# Toll_Controller_Unit_1st_Iteration.net
KiCad netlist of a schematic drawn in EAGLE
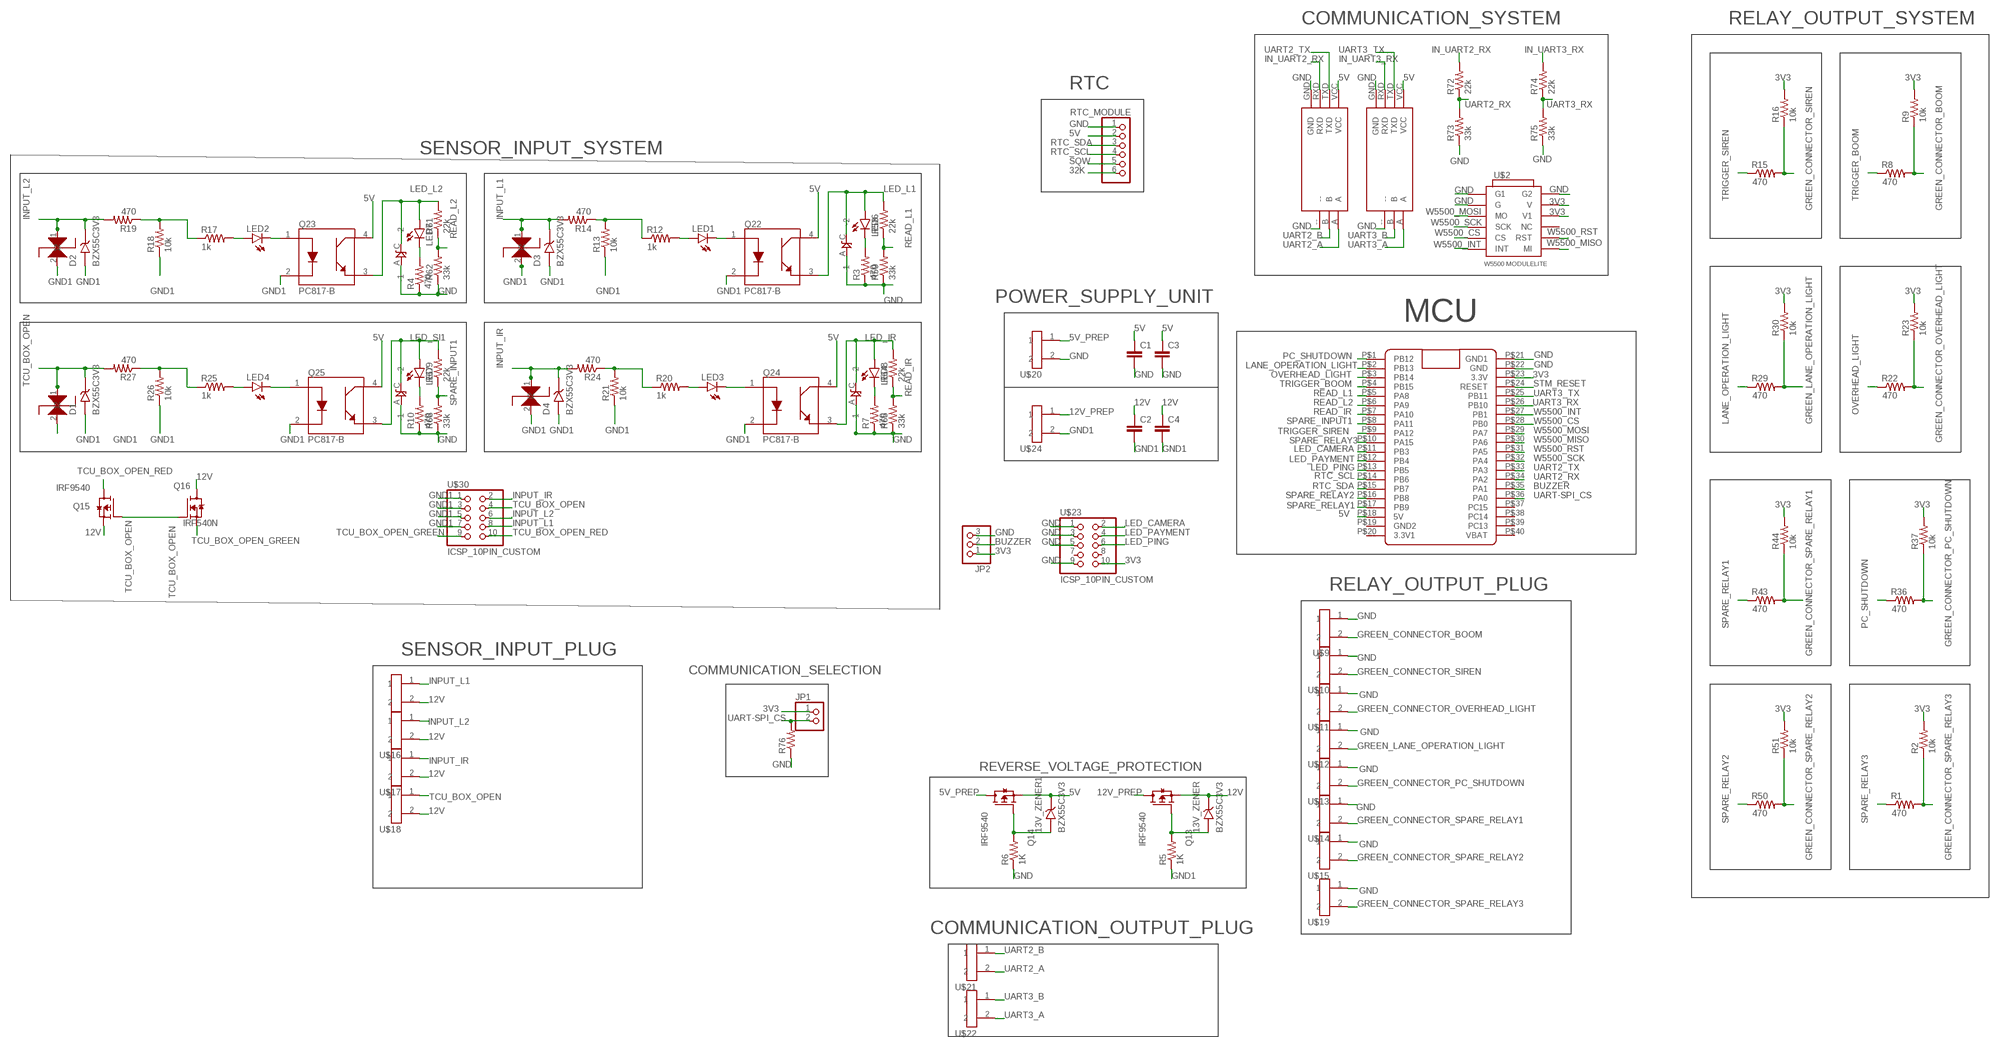
[diagram p0: schematic, sheet 1]

(export (version "E")
  (design (tool "Eeschema 10.0.6"))
  (components
    (comp (ref "13V_ZENER")
      (value "BZX55C3V3")
      (footprint "eagle-import:DIOAD928W47L399D179")
      (fields (field (name "MF") "Vishay Semiconductor") (field (name "MP") "BZX55C3V3-TR"))
      (libsource (lib "eagle-import") (part "BZX55C3V3"))
    )
    (comp (ref "13V_ZENER1")
      (value "BZX55C3V3")
      (footprint "eagle-import:DIOAD928W47L399D179")
      (fields (field (name "MF") "Vishay Semiconductor") (field (name "MP") "BZX55C3V3-TR"))
      (libsource (lib "eagle-import") (part "BZX55C3V3"))
    )
    (comp (ref "C1")
      (value "CAPACITOR")
      (footprint "eagle-import:CAPACITOR")
      (libsource (lib "eagle-import") (part "CAPACITOR"))
    )
    (comp (ref "C2")
      (value "CAPACITOR")
      (footprint "eagle-import:CAPACITOR")
      (libsource (lib "eagle-import") (part "CAPACITOR"))
    )
    (comp (ref "C3")
      (value "CAPACITOR")
      (footprint "eagle-import:CAPACITOR")
      (libsource (lib "eagle-import") (part "CAPACITOR"))
    )
    (comp (ref "C4")
      (value "CAPACITOR")
      (footprint "eagle-import:CAPACITOR")
      (libsource (lib "eagle-import") (part "CAPACITOR"))
    )
    (comp (ref "D1")
      (value "BZX55C3V3")
      (footprint "eagle-import:DIOAD928W47L399D179")
      (fields (field (name "MF") "Vishay Semiconductor") (field (name "MP") "BZX55C3V3-TR"))
      (libsource (lib "eagle-import") (part "BZX55C3V3"))
    )
    (comp (ref "D2")
      (value "BZX55C3V3")
      (footprint "eagle-import:DIOAD928W47L399D179")
      (fields (field (name "MF") "Vishay Semiconductor") (field (name "MP") "BZX55C3V3-TR"))
      (libsource (lib "eagle-import") (part "BZX55C3V3"))
    )
    (comp (ref "D3")
      (value "BZX55C3V3")
      (footprint "eagle-import:DIOAD928W47L399D179")
      (fields (field (name "MF") "Vishay Semiconductor") (field (name "MP") "BZX55C3V3-TR"))
      (libsource (lib "eagle-import") (part "BZX55C3V3"))
    )
    (comp (ref "D4")
      (value "BZX55C3V3")
      (footprint "eagle-import:DIOAD928W47L399D179")
      (fields (field (name "MF") "Vishay Semiconductor") (field (name "MP") "BZX55C3V3-TR"))
      (libsource (lib "eagle-import") (part "BZX55C3V3"))
    )
    (comp (ref "JP1")
      (value "PINHD-1X2")
      (footprint "eagle-import:1X02")
      (libsource (lib "eagle-import") (part "PINHD-1X2"))
    )
    (comp (ref "JP2")
      (value "PINHD-1X3")
      (footprint "eagle-import:1X03")
      (libsource (lib "eagle-import") (part "PINHD-1X3"))
    )
    (comp (ref "LED1")
      (value "LED")
      (footprint "eagle-import:LED")
      (libsource (lib "eagle-import") (part "LED"))
    )
    (comp (ref "LED2")
      (value "LED")
      (footprint "eagle-import:LED")
      (libsource (lib "eagle-import") (part "LED"))
    )
    (comp (ref "LED3")
      (value "LED")
      (footprint "eagle-import:LED")
      (libsource (lib "eagle-import") (part "LED"))
    )
    (comp (ref "LED4")
      (value "LED")
      (footprint "eagle-import:LED")
      (libsource (lib "eagle-import") (part "LED"))
    )
    (comp (ref "LED6")
      (value "LED")
      (footprint "eagle-import:LED")
      (libsource (lib "eagle-import") (part "LED"))
    )
    (comp (ref "LED7")
      (value "LED")
      (footprint "eagle-import:LED")
      (libsource (lib "eagle-import") (part "LED"))
    )
    (comp (ref "LED8")
      (value "LED")
      (footprint "eagle-import:LED")
      (libsource (lib "eagle-import") (part "LED"))
    )
    (comp (ref "LED9")
      (value "LED")
      (footprint "eagle-import:LED")
      (libsource (lib "eagle-import") (part "LED"))
    )
    (comp (ref "Q13")
      (value "IRF9540")
      (footprint "eagle-import:TO254P1052X465X1989-3")
      (fields (field (name "MF") "Vishay Siliconix"))
      (libsource (lib "eagle-import") (part "IRF9540"))
    )
    (comp (ref "Q14")
      (value "IRF9540")
      (footprint "eagle-import:TO254P1052X465X1989-3")
      (fields (field (name "MF") "Vishay Siliconix"))
      (libsource (lib "eagle-import") (part "IRF9540"))
    )
    (comp (ref "Q15")
      (value "IRF9540")
      (footprint "eagle-import:TO254P1052X465X1989-3")
      (fields (field (name "MF") "Vishay Siliconix"))
      (libsource (lib "eagle-import") (part "IRF9540"))
    )
    (comp (ref "Q16")
      (value "IRF540N")
      (footprint "eagle-import:TO254P1054X469X1930-3")
      (fields (field (name "MF") "Infineon Technologies"))
      (libsource (lib "eagle-import") (part "IRF540N"))
    )
    (comp (ref "Q22")
      (value "PC817-B")
      (footprint "eagle-import:DIP762W50P254L650H455Q4B")
      (fields (field (name "MF") "American Bright"))
      (libsource (lib "eagle-import") (part "PC817-B"))
    )
    (comp (ref "Q23")
      (value "PC817-B")
      (footprint "eagle-import:DIP762W50P254L650H455Q4B")
      (fields (field (name "MF") "American Bright"))
      (libsource (lib "eagle-import") (part "PC817-B"))
    )
    (comp (ref "Q24")
      (value "PC817-B")
      (footprint "eagle-import:DIP762W50P254L650H455Q4B")
      (fields (field (name "MF") "American Bright"))
      (libsource (lib "eagle-import") (part "PC817-B"))
    )
    (comp (ref "Q25")
      (value "PC817-B")
      (footprint "eagle-import:DIP762W50P254L650H455Q4B")
      (fields (field (name "MF") "American Bright"))
      (libsource (lib "eagle-import") (part "PC817-B"))
    )
    (comp (ref "R1")
      (value "470")
      (footprint "eagle-import:RESISTOR")
      (libsource (lib "eagle-import") (part "RESISTOR"))
    )
    (comp (ref "R2")
      (value "10k")
      (footprint "eagle-import:RESISTOR")
      (libsource (lib "eagle-import") (part "RESISTOR"))
    )
    (comp (ref "R3")
      (value "470")
      (footprint "eagle-import:RESISTOR")
      (libsource (lib "eagle-import") (part "RESISTOR"))
    )
    (comp (ref "R4")
      (value "470")
      (footprint "eagle-import:RESISTOR")
      (libsource (lib "eagle-import") (part "RESISTOR"))
    )
    (comp (ref "R5")
      (value "1K")
      (footprint "eagle-import:RESISTOR")
      (libsource (lib "eagle-import") (part "RESISTOR"))
    )
    (comp (ref "R6")
      (value "1K")
      (footprint "eagle-import:RESISTOR")
      (libsource (lib "eagle-import") (part "RESISTOR"))
    )
    (comp (ref "R7")
      (value "470")
      (footprint "eagle-import:RESISTOR")
      (libsource (lib "eagle-import") (part "RESISTOR"))
    )
    (comp (ref "R8")
      (value "470")
      (footprint "eagle-import:RESISTOR")
      (libsource (lib "eagle-import") (part "RESISTOR"))
    )
    (comp (ref "R9")
      (value "10k")
      (footprint "eagle-import:RESISTOR")
      (libsource (lib "eagle-import") (part "RESISTOR"))
    )
    (comp (ref "R10")
      (value "470")
      (footprint "eagle-import:RESISTOR")
      (libsource (lib "eagle-import") (part "RESISTOR"))
    )
    (comp (ref "R12")
      (value "1k")
      (footprint "eagle-import:RESISTOR")
      (libsource (lib "eagle-import") (part "RESISTOR"))
    )
    (comp (ref "R13")
      (value "10k")
      (footprint "eagle-import:RESISTOR")
      (libsource (lib "eagle-import") (part "RESISTOR"))
    )
    (comp (ref "R14")
      (value "470")
      (footprint "eagle-import:RESISTOR")
      (libsource (lib "eagle-import") (part "RESISTOR"))
    )
    (comp (ref "R15")
      (value "470")
      (footprint "eagle-import:RESISTOR")
      (libsource (lib "eagle-import") (part "RESISTOR"))
    )
    (comp (ref "R16")
      (value "10k")
      (footprint "eagle-import:RESISTOR")
      (libsource (lib "eagle-import") (part "RESISTOR"))
    )
    (comp (ref "R17")
      (value "1k")
      (footprint "eagle-import:RESISTOR")
      (libsource (lib "eagle-import") (part "RESISTOR"))
    )
    (comp (ref "R18")
      (value "10k")
      (footprint "eagle-import:RESISTOR")
      (libsource (lib "eagle-import") (part "RESISTOR"))
    )
    (comp (ref "R19")
      (value "470")
      (footprint "eagle-import:RESISTOR")
      (libsource (lib "eagle-import") (part "RESISTOR"))
    )
    (comp (ref "R20")
      (value "1k")
      (footprint "eagle-import:RESISTOR")
      (libsource (lib "eagle-import") (part "RESISTOR"))
    )
    (comp (ref "R21")
      (value "10k")
      (footprint "eagle-import:RESISTOR")
      (libsource (lib "eagle-import") (part "RESISTOR"))
    )
    (comp (ref "R22")
      (value "470")
      (footprint "eagle-import:RESISTOR")
      (libsource (lib "eagle-import") (part "RESISTOR"))
    )
    (comp (ref "R23")
      (value "10k")
      (footprint "eagle-import:RESISTOR")
      (libsource (lib "eagle-import") (part "RESISTOR"))
    )
    (comp (ref "R24")
      (value "470")
      (footprint "eagle-import:RESISTOR")
      (libsource (lib "eagle-import") (part "RESISTOR"))
    )
    (comp (ref "R25")
      (value "1k")
      (footprint "eagle-import:RESISTOR")
      (libsource (lib "eagle-import") (part "RESISTOR"))
    )
    (comp (ref "R26")
      (value "10k")
      (footprint "eagle-import:RESISTOR")
      (libsource (lib "eagle-import") (part "RESISTOR"))
    )
    (comp (ref "R27")
      (value "470")
      (footprint "eagle-import:RESISTOR")
      (libsource (lib "eagle-import") (part "RESISTOR"))
    )
    (comp (ref "R29")
      (value "470")
      (footprint "eagle-import:RESISTOR")
      (libsource (lib "eagle-import") (part "RESISTOR"))
    )
    (comp (ref "R30")
      (value "10k")
      (footprint "eagle-import:RESISTOR")
      (libsource (lib "eagle-import") (part "RESISTOR"))
    )
    (comp (ref "R36")
      (value "470")
      (footprint "eagle-import:RESISTOR")
      (libsource (lib "eagle-import") (part "RESISTOR"))
    )
    (comp (ref "R37")
      (value "10k")
      (footprint "eagle-import:RESISTOR")
      (libsource (lib "eagle-import") (part "RESISTOR"))
    )
    (comp (ref "R43")
      (value "470")
      (footprint "eagle-import:RESISTOR")
      (libsource (lib "eagle-import") (part "RESISTOR"))
    )
    (comp (ref "R44")
      (value "10k")
      (footprint "eagle-import:RESISTOR")
      (libsource (lib "eagle-import") (part "RESISTOR"))
    )
    (comp (ref "R50")
      (value "470")
      (footprint "eagle-import:RESISTOR")
      (libsource (lib "eagle-import") (part "RESISTOR"))
    )
    (comp (ref "R51")
      (value "10k")
      (footprint "eagle-import:RESISTOR")
      (libsource (lib "eagle-import") (part "RESISTOR"))
    )
    (comp (ref "R58")
      (value "22k")
      (footprint "eagle-import:RESISTOR")
      (libsource (lib "eagle-import") (part "RESISTOR"))
    )
    (comp (ref "R59")
      (value "33k")
      (footprint "eagle-import:RESISTOR")
      (libsource (lib "eagle-import") (part "RESISTOR"))
    )
    (comp (ref "R61")
      (value "22k")
      (footprint "eagle-import:RESISTOR")
      (libsource (lib "eagle-import") (part "RESISTOR"))
    )
    (comp (ref "R62")
      (value "33k")
      (footprint "eagle-import:RESISTOR")
      (libsource (lib "eagle-import") (part "RESISTOR"))
    )
    (comp (ref "R64")
      (value "22k")
      (footprint "eagle-import:RESISTOR")
      (libsource (lib "eagle-import") (part "RESISTOR"))
    )
    (comp (ref "R65")
      (value "33k")
      (footprint "eagle-import:RESISTOR")
      (libsource (lib "eagle-import") (part "RESISTOR"))
    )
    (comp (ref "R67")
      (value "22k")
      (footprint "eagle-import:RESISTOR")
      (libsource (lib "eagle-import") (part "RESISTOR"))
    )
    (comp (ref "R68")
      (value "33k")
      (footprint "eagle-import:RESISTOR")
      (libsource (lib "eagle-import") (part "RESISTOR"))
    )
    (comp (ref "R72")
      (value "22k")
      (footprint "eagle-import:RESISTOR")
      (libsource (lib "eagle-import") (part "RESISTOR"))
    )
    (comp (ref "R73")
      (value "33k")
      (footprint "eagle-import:RESISTOR")
      (libsource (lib "eagle-import") (part "RESISTOR"))
    )
    (comp (ref "R74")
      (value "22k")
      (footprint "eagle-import:RESISTOR")
      (libsource (lib "eagle-import") (part "RESISTOR"))
    )
    (comp (ref "R75")
      (value "33k")
      (footprint "eagle-import:RESISTOR")
      (libsource (lib "eagle-import") (part "RESISTOR"))
    )
    (comp (ref "R76")
      (value "RESISTOR")
      (footprint "eagle-import:RESISTOR")
      (libsource (lib "eagle-import") (part "RESISTOR"))
    )
    (comp (ref "RTC_MODULE")
      (value "PINHD-1X6")
      (footprint "eagle-import:1X06")
      (libsource (lib "eagle-import") (part "PINHD-1X6"))
    )
    (comp (ref "STM_BLUEPILL")
      (value "BLUE_PILL")
      (footprint "eagle-import:BLUE_PILL")
      (libsource (lib "eagle-import") (part "BLUE_PILL"))
    )
    (comp (ref "U$1")
      (value "1N227B")
      (footprint "eagle-import:1N227B")
      (libsource (lib "eagle-import") (part "1N227B"))
    )
    (comp (ref "U$2")
      (value "W5500_MODULELITE")
      (footprint "eagle-import:W5500_MODULELITE")
      (libsource (lib "eagle-import") (part "W5500_MODULELITE"))
    )
    (comp (ref "U$3")
      (value "1N227B")
      (footprint "eagle-import:1N227B")
      (libsource (lib "eagle-import") (part "1N227B"))
    )
    (comp (ref "U$4")
      (value "1N227B")
      (footprint "eagle-import:1N227B")
      (libsource (lib "eagle-import") (part "1N227B"))
    )
    (comp (ref "U$5")
      (value "1N227B")
      (footprint "eagle-import:1N227B")
      (libsource (lib "eagle-import") (part "1N227B"))
    )
    (comp (ref "U$6")
      (value "GREEN_PLUG_90_2")
      (footprint "eagle-import:GREEN_PLUG_90_2")
      (libsource (lib "eagle-import") (part "GREEN_PLUG_90_2"))
    )
    (comp (ref "U$7")
      (value "RS485_CHINESE")
      (footprint "eagle-import:RS485_CHINESE")
      (libsource (lib "eagle-import") (part "RS485_CHINESE"))
    )
    (comp (ref "U$8")
      (value "RS485_CHINESE")
      (footprint "eagle-import:RS485_CHINESE")
      (libsource (lib "eagle-import") (part "RS485_CHINESE"))
    )
    (comp (ref "U$9")
      (value "GREEN_PLUG_90_2")
      (footprint "eagle-import:GREEN_PLUG_90_2")
      (libsource (lib "eagle-import") (part "GREEN_PLUG_90_2"))
    )
    (comp (ref "U$10")
      (value "GREEN_PLUG_90_2")
      (footprint "eagle-import:GREEN_PLUG_90_2")
      (libsource (lib "eagle-import") (part "GREEN_PLUG_90_2"))
    )
    (comp (ref "U$11")
      (value "GREEN_PLUG_90_2")
      (footprint "eagle-import:GREEN_PLUG_90_2")
      (libsource (lib "eagle-import") (part "GREEN_PLUG_90_2"))
    )
    (comp (ref "U$12")
      (value "GREEN_PLUG_90_2")
      (footprint "eagle-import:GREEN_PLUG_90_2")
      (libsource (lib "eagle-import") (part "GREEN_PLUG_90_2"))
    )
    (comp (ref "U$13")
      (value "GREEN_PLUG_90_2")
      (footprint "eagle-import:GREEN_PLUG_90_2")
      (libsource (lib "eagle-import") (part "GREEN_PLUG_90_2"))
    )
    (comp (ref "U$14")
      (value "GREEN_PLUG_90_2")
      (footprint "eagle-import:GREEN_PLUG_90_2")
      (libsource (lib "eagle-import") (part "GREEN_PLUG_90_2"))
    )
    (comp (ref "U$15")
      (value "GREEN_PLUG_90_2")
      (footprint "eagle-import:GREEN_PLUG_90_2")
      (libsource (lib "eagle-import") (part "GREEN_PLUG_90_2"))
    )
    (comp (ref "U$16")
      (value "GREEN_PLUG_90_2")
      (footprint "eagle-import:GREEN_PLUG_90_2")
      (libsource (lib "eagle-import") (part "GREEN_PLUG_90_2"))
    )
    (comp (ref "U$17")
      (value "GREEN_PLUG_90_2")
      (footprint "eagle-import:GREEN_PLUG_90_2")
      (libsource (lib "eagle-import") (part "GREEN_PLUG_90_2"))
    )
    (comp (ref "U$18")
      (value "GREEN_PLUG_90_2")
      (footprint "eagle-import:GREEN_PLUG_90_2")
      (libsource (lib "eagle-import") (part "GREEN_PLUG_90_2"))
    )
    (comp (ref "U$19")
      (value "GREEN_PLUG_90_2")
      (footprint "eagle-import:GREEN_PLUG_90_2")
      (libsource (lib "eagle-import") (part "GREEN_PLUG_90_2"))
    )
    (comp (ref "U$20")
      (value "GREEN_PLUG_90_2")
      (footprint "eagle-import:GREEN_PLUG_90_2")
      (libsource (lib "eagle-import") (part "GREEN_PLUG_90_2"))
    )
    (comp (ref "U$21")
      (value "GREEN_PLUG_90_2")
      (footprint "eagle-import:GREEN_PLUG_90_2")
      (libsource (lib "eagle-import") (part "GREEN_PLUG_90_2"))
    )
    (comp (ref "U$22")
      (value "GREEN_PLUG_90_2")
      (footprint "eagle-import:GREEN_PLUG_90_2")
      (libsource (lib "eagle-import") (part "GREEN_PLUG_90_2"))
    )
    (comp (ref "U$23")
      (value "ICSP_10PIN_CUSTOM")
      (footprint "eagle-import:ICSP_10PIN_CUSTOM")
      (libsource (lib "eagle-import") (part "ICSP_10PIN_CUSTOM"))
    )
    (comp (ref "U$24")
      (value "GREEN_PLUG_90_2")
      (footprint "eagle-import:GREEN_PLUG_90_2")
      (libsource (lib "eagle-import") (part "GREEN_PLUG_90_2"))
    )
    (comp (ref "U$25")
      (value "1KE100A_CUSTOM")
      (footprint "eagle-import:1KE100A_CUSTOM")
      (libsource (lib "eagle-import") (part "1KE100A_CUSTOM"))
    )
    (comp (ref "U$26")
      (value "1KE100A_CUSTOM")
      (footprint "eagle-import:1KE100A_CUSTOM")
      (libsource (lib "eagle-import") (part "1KE100A_CUSTOM"))
    )
    (comp (ref "U$27")
      (value "1KE100A_CUSTOM")
      (footprint "eagle-import:1KE100A_CUSTOM")
      (libsource (lib "eagle-import") (part "1KE100A_CUSTOM"))
    )
    (comp (ref "U$28")
      (value "1KE100A_CUSTOM")
      (footprint "eagle-import:1KE100A_CUSTOM")
      (libsource (lib "eagle-import") (part "1KE100A_CUSTOM"))
    )
    (comp (ref "U$30")
      (value "ICSP_10PIN_CUSTOM")
      (footprint "eagle-import:ICSP_10PIN_CUSTOM")
      (libsource (lib "eagle-import") (part "ICSP_10PIN_CUSTOM"))
    )
  )
  (nets
    (net (code "1") (name "/3V3") (class "Default")
      (node (ref "JP1") (pin "1") (pinfunction "1_1") (pintype "passive"))
      (node (ref "JP2") (pin "1") (pinfunction "1_1") (pintype "passive"))
      (node (ref "R16") (pin "2") (pinfunction "2_2") (pintype "passive"))
      (node (ref "R2") (pin "2") (pinfunction "2_2") (pintype "passive"))
      (node (ref "R23") (pin "2") (pinfunction "2_2") (pintype "passive"))
      (node (ref "R30") (pin "2") (pinfunction "2_2") (pintype "passive"))
      (node (ref "R37") (pin "2") (pinfunction "2_2") (pintype "passive"))
      (node (ref "R44") (pin "2") (pinfunction "2_2") (pintype "passive"))
      (node (ref "R51") (pin "2") (pinfunction "2_2") (pintype "passive"))
      (node (ref "R9") (pin "2") (pinfunction "2_2") (pintype "passive"))
      (node (ref "STM_BLUEPILL") (pin "P$23") (pinfunction "3.3V_P$23") (pintype "bidirectional"))
      (node (ref "U$2") (pin "V") (pinfunction "V_V") (pintype "passive"))
      (node (ref "U$2") (pin "V1") (pinfunction "V1_V1") (pintype "passive"))
      (node (ref "U$23") (pin "10") (pinfunction "10_10") (pintype "passive"))
    )
    (net (code "2") (name "/5V") (class "Default")
      (node (ref "13V_ZENER1") (pin "C") (pinfunction "K_C") (pintype "passive"))
      (node (ref "C1") (pin "1") (pinfunction "1_1") (pintype "passive"))
      (node (ref "C3") (pin "1") (pinfunction "1_1") (pintype "passive"))
      (node (ref "Q14") (pin "3") (pinfunction "S_3") (pintype "passive"))
      (node (ref "Q22") (pin "4") (pinfunction "COLLECTOR_4") (pintype "passive"))
      (node (ref "Q23") (pin "4") (pinfunction "COLLECTOR_4") (pintype "passive"))
      (node (ref "Q24") (pin "4") (pinfunction "COLLECTOR_4") (pintype "passive"))
      (node (ref "Q25") (pin "4") (pinfunction "COLLECTOR_4") (pintype "passive"))
      (node (ref "RTC_MODULE") (pin "2") (pinfunction "2_2") (pintype "passive"))
      (node (ref "STM_BLUEPILL") (pin "P$18") (pinfunction "5V_P$18") (pintype "bidirectional"))
      (node (ref "U$7") (pin "VCC") (pinfunction "VCC_VCC") (pintype "bidirectional"))
      (node (ref "U$8") (pin "VCC") (pinfunction "VCC_VCC") (pintype "bidirectional"))
    )
    (net (code "3") (name "/5V_PREP") (class "Default")
      (node (ref "Q14") (pin "2") (pinfunction "D_2") (pintype "passive"))
      (node (ref "U$20") (pin "1") (pinfunction "1_1") (pintype "passive"))
    )
    (net (code "4") (name "/12V") (class "Default")
      (node (ref "13V_ZENER") (pin "C") (pinfunction "K_C") (pintype "passive"))
      (node (ref "C2") (pin "1") (pinfunction "1_1") (pintype "passive"))
      (node (ref "C4") (pin "1") (pinfunction "1_1") (pintype "passive"))
      (node (ref "Q13") (pin "3") (pinfunction "S_3") (pintype "passive"))
      (node (ref "Q15") (pin "3") (pinfunction "S_3") (pintype "passive"))
      (node (ref "Q16") (pin "2") (pinfunction "D_2") (pintype "passive"))
      (node (ref "U$16") (pin "2") (pinfunction "2_2") (pintype "passive"))
      (node (ref "U$17") (pin "2") (pinfunction "2_2") (pintype "passive"))
      (node (ref "U$18") (pin "2") (pinfunction "2_2") (pintype "passive"))
      (node (ref "U$6") (pin "2") (pinfunction "2_2") (pintype "passive"))
    )
    (net (code "5") (name "/12V_PREP") (class "Default")
      (node (ref "Q13") (pin "2") (pinfunction "D_2") (pintype "passive"))
      (node (ref "U$24") (pin "1") (pinfunction "1_1") (pintype "passive"))
    )
    (net (code "6") (name "/32K") (class "Default")
      (node (ref "RTC_MODULE") (pin "6") (pinfunction "6_6") (pintype "passive"))
    )
    (net (code "7") (name "/BUZZER") (class "Default")
      (node (ref "JP2") (pin "2") (pinfunction "2_2") (pintype "passive"))
      (node (ref "STM_BLUEPILL") (pin "P$35") (pinfunction "PA1_P$35") (pintype "bidirectional"))
    )
    (net (code "8") (name "/GND") (class "Default")
      (node (ref "C1") (pin "2") (pinfunction "2_2") (pintype "passive"))
      (node (ref "C3") (pin "2") (pinfunction "2_2") (pintype "passive"))
      (node (ref "JP2") (pin "3") (pinfunction "3_3") (pintype "passive"))
      (node (ref "R10") (pin "1") (pinfunction "1_1") (pintype "passive"))
      (node (ref "R3") (pin "1") (pinfunction "1_1") (pintype "passive"))
      (node (ref "R4") (pin "1") (pinfunction "1_1") (pintype "passive"))
      (node (ref "R59") (pin "1") (pinfunction "1_1") (pintype "passive"))
      (node (ref "R6") (pin "1") (pinfunction "1_1") (pintype "passive"))
      (node (ref "R62") (pin "1") (pinfunction "1_1") (pintype "passive"))
      (node (ref "R65") (pin "1") (pinfunction "1_1") (pintype "passive"))
      (node (ref "R68") (pin "1") (pinfunction "1_1") (pintype "passive"))
      (node (ref "R7") (pin "1") (pinfunction "1_1") (pintype "passive"))
      (node (ref "R73") (pin "1") (pinfunction "1_1") (pintype "passive"))
      (node (ref "R75") (pin "1") (pinfunction "1_1") (pintype "passive"))
      (node (ref "R76") (pin "1") (pinfunction "1_1") (pintype "passive"))
      (node (ref "RTC_MODULE") (pin "1") (pinfunction "1_1") (pintype "passive"))
      (node (ref "STM_BLUEPILL") (pin "P$21") (pinfunction "GND1_P$21") (pintype "power_in"))
      (node (ref "STM_BLUEPILL") (pin "P$22") (pinfunction "GND_P$22") (pintype "bidirectional"))
      (node (ref "U$1") (pin "A") (pinfunction "-1_A") (pintype "passive"))
      (node (ref "U$10") (pin "1") (pinfunction "1_1") (pintype "passive"))
      (node (ref "U$11") (pin "1") (pinfunction "1_1") (pintype "passive"))
      (node (ref "U$12") (pin "1") (pinfunction "1_1") (pintype "passive"))
      (node (ref "U$13") (pin "1") (pinfunction "1_1") (pintype "passive"))
      (node (ref "U$14") (pin "1") (pinfunction "1_1") (pintype "passive"))
      (node (ref "U$15") (pin "1") (pinfunction "1_1") (pintype "passive"))
      (node (ref "U$19") (pin "1") (pinfunction "1_1") (pintype "passive"))
      (node (ref "U$2") (pin "G") (pinfunction "G_G") (pintype "passive"))
      (node (ref "U$2") (pin "G1") (pinfunction "G1_G1") (pintype "passive"))
      (node (ref "U$2") (pin "G2") (pinfunction "G2_G2") (pintype "passive"))
      (node (ref "U$20") (pin "2") (pinfunction "2_2") (pintype "passive"))
      (node (ref "U$23") (pin "1") (pinfunction "1_1") (pintype "passive"))
      (node (ref "U$23") (pin "3") (pinfunction "3_3") (pintype "passive"))
      (node (ref "U$23") (pin "5") (pinfunction "5_5") (pintype "passive"))
      (node (ref "U$23") (pin "9") (pinfunction "9_9") (pintype "passive"))
      (node (ref "U$3") (pin "A") (pinfunction "-1_A") (pintype "passive"))
      (node (ref "U$4") (pin "A") (pinfunction "-1_A") (pintype "passive"))
      (node (ref "U$5") (pin "A") (pinfunction "-1_A") (pintype "passive"))
      (node (ref "U$7") (pin "--") (pinfunction "--_--") (pintype "bidirectional"))
      (node (ref "U$7") (pin "GND") (pinfunction "GND_GND") (pintype "bidirectional"))
      (node (ref "U$8") (pin "--") (pinfunction "--_--") (pintype "bidirectional"))
      (node (ref "U$8") (pin "GND") (pinfunction "GND_GND") (pintype "bidirectional"))
      (node (ref "U$9") (pin "1") (pinfunction "1_1") (pintype "passive"))
    )
    (net (code "9") (name "/GND1") (class "Default")
      (node (ref "C2") (pin "2") (pinfunction "2_2") (pintype "passive"))
      (node (ref "C4") (pin "2") (pinfunction "2_2") (pintype "passive"))
      (node (ref "D1") (pin "A") (pinfunction "A_A") (pintype "passive"))
      (node (ref "D2") (pin "A") (pinfunction "A_A") (pintype "passive"))
      (node (ref "D3") (pin "A") (pinfunction "A_A") (pintype "passive"))
      (node (ref "D4") (pin "A") (pinfunction "A_A") (pintype "passive"))
      (node (ref "Q22") (pin "2") (pinfunction "CATHODE_2") (pintype "passive"))
      (node (ref "Q23") (pin "2") (pinfunction "CATHODE_2") (pintype "passive"))
      (node (ref "Q24") (pin "2") (pinfunction "CATHODE_2") (pintype "passive"))
      (node (ref "Q25") (pin "2") (pinfunction "CATHODE_2") (pintype "passive"))
      (node (ref "R13") (pin "1") (pinfunction "1_1") (pintype "passive"))
      (node (ref "R18") (pin "1") (pinfunction "1_1") (pintype "passive"))
      (node (ref "R21") (pin "1") (pinfunction "1_1") (pintype "passive"))
      (node (ref "R26") (pin "1") (pinfunction "1_1") (pintype "passive"))
      (node (ref "R5") (pin "1") (pinfunction "1_1") (pintype "passive"))
      (node (ref "U$24") (pin "2") (pinfunction "2_2") (pintype "passive"))
      (node (ref "U$25") (pin "2") (pinfunction "2_2") (pintype "bidirectional"))
      (node (ref "U$26") (pin "2") (pinfunction "2_2") (pintype "bidirectional"))
      (node (ref "U$30") (pin "1") (pinfunction "1_1") (pintype "passive"))
      (node (ref "U$30") (pin "3") (pinfunction "3_3") (pintype "passive"))
      (node (ref "U$30") (pin "5") (pinfunction "5_5") (pintype "passive"))
      (node (ref "U$30") (pin "7") (pinfunction "7_7") (pintype "passive"))
    )
    (net (code "10") (name "/GREEN_CONNECTOR_BOOM") (class "Default")
      (node (ref "R8") (pin "2") (pinfunction "2_2") (pintype "passive"))
      (node (ref "R9") (pin "1") (pinfunction "1_1") (pintype "passive"))
      (node (ref "U$9") (pin "2") (pinfunction "2_2") (pintype "passive"))
    )
    (net (code "11") (name "/GREEN_CONNECTOR_OVERHEAD_LIGHT") (class "Default")
      (node (ref "R22") (pin "2") (pinfunction "2_2") (pintype "passive"))
      (node (ref "R23") (pin "1") (pinfunction "1_1") (pintype "passive"))
      (node (ref "U$11") (pin "2") (pinfunction "2_2") (pintype "passive"))
    )
    (net (code "12") (name "/GREEN_CONNECTOR_PC_SHUTDOWN") (class "Default")
      (node (ref "R36") (pin "2") (pinfunction "2_2") (pintype "passive"))
      (node (ref "R37") (pin "1") (pinfunction "1_1") (pintype "passive"))
      (node (ref "U$13") (pin "2") (pinfunction "2_2") (pintype "passive"))
    )
    (net (code "13") (name "/GREEN_CONNECTOR_SIREN") (class "Default")
      (node (ref "R15") (pin "2") (pinfunction "2_2") (pintype "passive"))
      (node (ref "R16") (pin "1") (pinfunction "1_1") (pintype "passive"))
      (node (ref "U$10") (pin "2") (pinfunction "2_2") (pintype "passive"))
    )
    (net (code "14") (name "/GREEN_CONNECTOR_SPARE_RELAY1") (class "Default")
      (node (ref "R43") (pin "2") (pinfunction "2_2") (pintype "passive"))
      (node (ref "R44") (pin "1") (pinfunction "1_1") (pintype "passive"))
      (node (ref "U$14") (pin "2") (pinfunction "2_2") (pintype "passive"))
    )
    (net (code "15") (name "/GREEN_CONNECTOR_SPARE_RELAY2") (class "Default")
      (node (ref "R50") (pin "2") (pinfunction "2_2") (pintype "passive"))
      (node (ref "R51") (pin "1") (pinfunction "1_1") (pintype "passive"))
      (node (ref "U$15") (pin "2") (pinfunction "2_2") (pintype "passive"))
    )
    (net (code "16") (name "/GREEN_CONNECTOR_SPARE_RELAY3") (class "Default")
      (node (ref "R1") (pin "2") (pinfunction "2_2") (pintype "passive"))
      (node (ref "R2") (pin "1") (pinfunction "1_1") (pintype "passive"))
      (node (ref "U$19") (pin "2") (pinfunction "2_2") (pintype "passive"))
    )
    (net (code "17") (name "/GREEN_LANE_OPERATION_LIGHT") (class "Default")
      (node (ref "R29") (pin "2") (pinfunction "2_2") (pintype "passive"))
      (node (ref "R30") (pin "1") (pinfunction "1_1") (pintype "passive"))
      (node (ref "U$12") (pin "2") (pinfunction "2_2") (pintype "passive"))
    )
    (net (code "18") (name "/INPUT_IR") (class "Default")
      (node (ref "D4") (pin "C") (pinfunction "K_C") (pintype "passive"))
      (node (ref "R24") (pin "2") (pinfunction "2_2") (pintype "passive"))
      (node (ref "U$17") (pin "1") (pinfunction "1_1") (pintype "passive"))
      (node (ref "U$27") (pin "1") (pinfunction "1_1") (pintype "bidirectional"))
      (node (ref "U$30") (pin "2") (pinfunction "2_2") (pintype "passive"))
    )
    (net (code "19") (name "/INPUT_L1") (class "Default")
      (node (ref "D3") (pin "C") (pinfunction "K_C") (pintype "passive"))
      (node (ref "R14") (pin "2") (pinfunction "2_2") (pintype "passive"))
      (node (ref "U$25") (pin "1") (pinfunction "1_1") (pintype "bidirectional"))
      (node (ref "U$30") (pin "8") (pinfunction "8_8") (pintype "passive"))
      (node (ref "U$6") (pin "1") (pinfunction "1_1") (pintype "passive"))
    )
    (net (code "20") (name "/INPUT_L2") (class "Default")
      (node (ref "D2") (pin "C") (pinfunction "K_C") (pintype "passive"))
      (node (ref "R19") (pin "2") (pinfunction "2_2") (pintype "passive"))
      (node (ref "U$16") (pin "1") (pinfunction "1_1") (pintype "passive"))
      (node (ref "U$28") (pin "1") (pinfunction "1_1") (pintype "bidirectional"))
      (node (ref "U$30") (pin "6") (pinfunction "6_6") (pintype "passive"))
    )
    (net (code "21") (name "/IN_UART2_RX") (class "Default")
      (node (ref "R72") (pin "2") (pinfunction "2_2") (pintype "passive"))
      (node (ref "U$8") (pin "RXD") (pinfunction "RXD_RXD") (pintype "bidirectional"))
    )
    (net (code "22") (name "/IN_UART3_RX") (class "Default")
      (node (ref "R74") (pin "2") (pinfunction "2_2") (pintype "passive"))
      (node (ref "U$7") (pin "RXD") (pinfunction "RXD_RXD") (pintype "bidirectional"))
    )
    (net (code "23") (name "/LANE_OPERATION_LIGHT") (class "Default")
      (node (ref "R29") (pin "1") (pinfunction "1_1") (pintype "passive"))
      (node (ref "STM_BLUEPILL") (pin "P$2") (pinfunction "PB13_P$2") (pintype "bidirectional"))
    )
    (net (code "24") (name "/LED_CAMERA") (class "Default")
      (node (ref "STM_BLUEPILL") (pin "P$11") (pinfunction "PB3_P$11") (pintype "bidirectional"))
      (node (ref "U$23") (pin "2") (pinfunction "2_2") (pintype "passive"))
    )
    (net (code "25") (name "/LED_IR") (class "Default")
      (node (ref "LED8") (pin "A") (pinfunction "A_A") (pintype "passive"))
      (node (ref "Q24") (pin "3") (pinfunction "EMITTER_3") (pintype "passive"))
      (node (ref "R64") (pin "2") (pinfunction "2_2") (pintype "passive"))
      (node (ref "U$4") (pin "C") (pinfunction "-2_C") (pintype "bidirectional"))
    )
    (net (code "26") (name "/LED_L1") (class "Default")
      (node (ref "LED6") (pin "A") (pinfunction "A_A") (pintype "passive"))
      (node (ref "Q22") (pin "3") (pinfunction "EMITTER_3") (pintype "passive"))
      (node (ref "R58") (pin "2") (pinfunction "2_2") (pintype "passive"))
      (node (ref "U$1") (pin "C") (pinfunction "-2_C") (pintype "bidirectional"))
    )
    (net (code "27") (name "/LED_L2") (class "Default")
      (node (ref "LED7") (pin "A") (pinfunction "A_A") (pintype "passive"))
      (node (ref "Q23") (pin "3") (pinfunction "EMITTER_3") (pintype "passive"))
      (node (ref "R61") (pin "2") (pinfunction "2_2") (pintype "passive"))
      (node (ref "U$3") (pin "C") (pinfunction "-2_C") (pintype "bidirectional"))
    )
    (net (code "28") (name "/LED_PAYMENT") (class "Default")
      (node (ref "STM_BLUEPILL") (pin "P$12") (pinfunction "PB4_P$12") (pintype "bidirectional"))
      (node (ref "U$23") (pin "4") (pinfunction "4_4") (pintype "passive"))
    )
    (net (code "29") (name "/LED_PING") (class "Default")
      (node (ref "STM_BLUEPILL") (pin "P$13") (pinfunction "PB5_P$13") (pintype "bidirectional"))
      (node (ref "U$23") (pin "6") (pinfunction "6_6") (pintype "passive"))
    )
    (net (code "30") (name "/LED_SI1") (class "Default")
      (node (ref "LED9") (pin "A") (pinfunction "A_A") (pintype "passive"))
      (node (ref "Q25") (pin "3") (pinfunction "EMITTER_3") (pintype "passive"))
      (node (ref "R67") (pin "2") (pinfunction "2_2") (pintype "passive"))
      (node (ref "U$5") (pin "C") (pinfunction "-2_C") (pintype "bidirectional"))
    )
    (net (code "31") (name "/OVERHEAD_LIGHT") (class "Default")
      (node (ref "R22") (pin "1") (pinfunction "1_1") (pintype "passive"))
      (node (ref "STM_BLUEPILL") (pin "P$3") (pinfunction "PB14_P$3") (pintype "bidirectional"))
    )
    (net (code "32") (name "/PC_SHUTDOWN") (class "Default")
      (node (ref "R36") (pin "1") (pinfunction "1_1") (pintype "passive"))
      (node (ref "STM_BLUEPILL") (pin "P$1") (pinfunction "PB12_P$1") (pintype "bidirectional"))
    )
    (net (code "33") (name "/READ_IR") (class "Default")
      (node (ref "R64") (pin "1") (pinfunction "1_1") (pintype "passive"))
      (node (ref "R65") (pin "2") (pinfunction "2_2") (pintype "passive"))
      (node (ref "STM_BLUEPILL") (pin "P$7") (pinfunction "PA10_P$7") (pintype "bidirectional"))
    )
    (net (code "34") (name "/READ_L1") (class "Default")
      (node (ref "R58") (pin "1") (pinfunction "1_1") (pintype "passive"))
      (node (ref "R59") (pin "2") (pinfunction "2_2") (pintype "passive"))
      (node (ref "STM_BLUEPILL") (pin "P$5") (pinfunction "PA8_P$5") (pintype "bidirectional"))
    )
    (net (code "35") (name "/READ_L2") (class "Default")
      (node (ref "R61") (pin "1") (pinfunction "1_1") (pintype "passive"))
      (node (ref "R62") (pin "2") (pinfunction "2_2") (pintype "passive"))
      (node (ref "STM_BLUEPILL") (pin "P$6") (pinfunction "PA9_P$6") (pintype "bidirectional"))
    )
    (net (code "36") (name "/RTC_SCL") (class "Default")
      (node (ref "RTC_MODULE") (pin "4") (pinfunction "4_4") (pintype "passive"))
      (node (ref "STM_BLUEPILL") (pin "P$14") (pinfunction "PB6_P$14") (pintype "bidirectional"))
    )
    (net (code "37") (name "/RTC_SDA") (class "Default")
      (node (ref "RTC_MODULE") (pin "3") (pinfunction "3_3") (pintype "passive"))
      (node (ref "STM_BLUEPILL") (pin "P$15") (pinfunction "PB7_P$15") (pintype "bidirectional"))
    )
    (net (code "38") (name "/SPARE_INPUT1") (class "Default")
      (node (ref "R67") (pin "1") (pinfunction "1_1") (pintype "passive"))
      (node (ref "R68") (pin "2") (pinfunction "2_2") (pintype "passive"))
      (node (ref "STM_BLUEPILL") (pin "P$8") (pinfunction "PA11_P$8") (pintype "bidirectional"))
    )
    (net (code "39") (name "/SPARE_RELAY1") (class "Default")
      (node (ref "R43") (pin "1") (pinfunction "1_1") (pintype "passive"))
      (node (ref "STM_BLUEPILL") (pin "P$17") (pinfunction "PB9_P$17") (pintype "bidirectional"))
    )
    (net (code "40") (name "/SPARE_RELAY2") (class "Default")
      (node (ref "R50") (pin "1") (pinfunction "1_1") (pintype "passive"))
      (node (ref "STM_BLUEPILL") (pin "P$16") (pinfunction "PB8_P$16") (pintype "bidirectional"))
    )
    (net (code "41") (name "/SPARE_RELAY3") (class "Default")
      (node (ref "R1") (pin "1") (pinfunction "1_1") (pintype "passive"))
      (node (ref "STM_BLUEPILL") (pin "P$10") (pinfunction "PA15_P$10") (pintype "bidirectional"))
    )
    (net (code "42") (name "/SQW") (class "Default")
      (node (ref "RTC_MODULE") (pin "5") (pinfunction "5_5") (pintype "passive"))
    )
    (net (code "43") (name "/STM_RESET") (class "Default")
      (node (ref "STM_BLUEPILL") (pin "P$24") (pinfunction "RESET_P$24") (pintype "bidirectional"))
    )
    (net (code "44") (name "/TCU_BOX_OPEN") (class "Default")
      (node (ref "D1") (pin "C") (pinfunction "K_C") (pintype "passive"))
      (node (ref "Q15") (pin "1") (pinfunction "G_1") (pintype "passive"))
      (node (ref "Q16") (pin "1") (pinfunction "G_1") (pintype "passive"))
      (node (ref "R27") (pin "2") (pinfunction "2_2") (pintype "passive"))
      (node (ref "U$18") (pin "1") (pinfunction "1_1") (pintype "passive"))
      (node (ref "U$26") (pin "1") (pinfunction "1_1") (pintype "bidirectional"))
      (node (ref "U$30") (pin "4") (pinfunction "4_4") (pintype "passive"))
    )
    (net (code "45") (name "/TCU_BOX_OPEN_GREEN") (class "Default")
      (node (ref "Q16") (pin "3") (pinfunction "S_3") (pintype "passive"))
      (node (ref "U$30") (pin "9") (pinfunction "9_9") (pintype "passive"))
    )
    (net (code "46") (name "/TCU_BOX_OPEN_RED") (class "Default")
      (node (ref "Q15") (pin "2") (pinfunction "D_2") (pintype "passive"))
      (node (ref "U$30") (pin "10") (pinfunction "10_10") (pintype "passive"))
    )
    (net (code "47") (name "/TRIGGER_BOOM") (class "Default")
      (node (ref "R8") (pin "1") (pinfunction "1_1") (pintype "passive"))
      (node (ref "STM_BLUEPILL") (pin "P$4") (pinfunction "PB15_P$4") (pintype "bidirectional"))
    )
    (net (code "48") (name "/TRIGGER_SIREN") (class "Default")
      (node (ref "R15") (pin "1") (pinfunction "1_1") (pintype "passive"))
      (node (ref "STM_BLUEPILL") (pin "P$9") (pinfunction "PA12_P$9") (pintype "bidirectional"))
    )
    (net (code "49") (name "/UART-SPI_CS") (class "Default")
      (node (ref "JP1") (pin "2") (pinfunction "2_2") (pintype "passive"))
      (node (ref "R76") (pin "2") (pinfunction "2_2") (pintype "passive"))
      (node (ref "STM_BLUEPILL") (pin "P$36") (pinfunction "PA0_P$36") (pintype "bidirectional"))
    )
    (net (code "50") (name "/UART2_A") (class "Default")
      (node (ref "U$21") (pin "2") (pinfunction "2_2") (pintype "passive"))
      (node (ref "U$8") (pin "A") (pinfunction "A_A") (pintype "bidirectional"))
    )
    (net (code "51") (name "/UART2_B") (class "Default")
      (node (ref "U$21") (pin "1") (pinfunction "1_1") (pintype "passive"))
      (node (ref "U$8") (pin "B") (pinfunction "B_B") (pintype "bidirectional"))
    )
    (net (code "52") (name "/UART2_RX") (class "Default")
      (node (ref "R72") (pin "1") (pinfunction "1_1") (pintype "passive"))
      (node (ref "R73") (pin "2") (pinfunction "2_2") (pintype "passive"))
      (node (ref "STM_BLUEPILL") (pin "P$34") (pinfunction "PA2_P$34") (pintype "bidirectional"))
    )
    (net (code "53") (name "/UART2_TX") (class "Default")
      (node (ref "STM_BLUEPILL") (pin "P$33") (pinfunction "PA3_P$33") (pintype "bidirectional"))
      (node (ref "U$8") (pin "TXD") (pinfunction "TXD_TXD") (pintype "bidirectional"))
    )
    (net (code "54") (name "/UART3_A") (class "Default")
      (node (ref "U$22") (pin "2") (pinfunction "2_2") (pintype "passive"))
      (node (ref "U$7") (pin "A") (pinfunction "A_A") (pintype "bidirectional"))
    )
    (net (code "55") (name "/UART3_B") (class "Default")
      (node (ref "U$22") (pin "1") (pinfunction "1_1") (pintype "passive"))
      (node (ref "U$7") (pin "B") (pinfunction "B_B") (pintype "bidirectional"))
    )
    (net (code "56") (name "/UART3_RX") (class "Default")
      (node (ref "R74") (pin "1") (pinfunction "1_1") (pintype "passive"))
      (node (ref "R75") (pin "2") (pinfunction "2_2") (pintype "passive"))
      (node (ref "STM_BLUEPILL") (pin "P$26") (pinfunction "PB10_P$26") (pintype "bidirectional"))
    )
    (net (code "57") (name "/UART3_TX") (class "Default")
      (node (ref "STM_BLUEPILL") (pin "P$25") (pinfunction "PB11_P$25") (pintype "bidirectional"))
      (node (ref "U$7") (pin "TXD") (pinfunction "TXD_TXD") (pintype "bidirectional"))
    )
    (net (code "58") (name "/W5500_CS") (class "Default")
      (node (ref "STM_BLUEPILL") (pin "P$28") (pinfunction "PB0_P$28") (pintype "bidirectional"))
      (node (ref "U$2") (pin "CS") (pinfunction "CS_CS") (pintype "passive"))
    )
    (net (code "59") (name "/W5500_INT") (class "Default")
      (node (ref "STM_BLUEPILL") (pin "P$27") (pinfunction "PB1_P$27") (pintype "bidirectional"))
      (node (ref "U$2") (pin "INT") (pinfunction "INT_INT") (pintype "passive"))
    )
    (net (code "60") (name "/W5500_MISO") (class "Default")
      (node (ref "STM_BLUEPILL") (pin "P$30") (pinfunction "PA6_P$30") (pintype "bidirectional"))
      (node (ref "U$2") (pin "MI") (pinfunction "MI_MI") (pintype "passive"))
    )
    (net (code "61") (name "/W5500_MOSI") (class "Default")
      (node (ref "STM_BLUEPILL") (pin "P$29") (pinfunction "PA7_P$29") (pintype "bidirectional"))
      (node (ref "U$2") (pin "MO") (pinfunction "MO_MO") (pintype "passive"))
    )
    (net (code "62") (name "/W5500_RST") (class "Default")
      (node (ref "STM_BLUEPILL") (pin "P$31") (pinfunction "PA5_P$31") (pintype "bidirectional"))
      (node (ref "U$2") (pin "RST") (pinfunction "RST_RST") (pintype "passive"))
    )
    (net (code "63") (name "/W5500_SCK") (class "Default")
      (node (ref "STM_BLUEPILL") (pin "P$32") (pinfunction "PA4_P$32") (pintype "bidirectional"))
      (node (ref "U$2") (pin "SCK") (pinfunction "SCK_SCK") (pintype "passive"))
    )
    (net (code "64") (name "Net-(LED1-C)") (class "Default")
      (node (ref "LED1") (pin "K") (pinfunction "C_K") (pintype "passive"))
      (node (ref "Q22") (pin "1") (pinfunction "ANODE_1") (pintype "passive"))
    )
    (net (code "65") (name "Net-(LED1-PadA)") (class "Default")
      (node (ref "LED1") (pin "A") (pinfunction "A_A") (pintype "passive"))
      (node (ref "R12") (pin "2") (pinfunction "2_2") (pintype "passive"))
    )
    (net (code "66") (name "Net-(LED2-C)") (class "Default")
      (node (ref "LED2") (pin "K") (pinfunction "C_K") (pintype "passive"))
      (node (ref "Q23") (pin "1") (pinfunction "ANODE_1") (pintype "passive"))
    )
    (net (code "67") (name "Net-(LED2-PadA)") (class "Default")
      (node (ref "LED2") (pin "A") (pinfunction "A_A") (pintype "passive"))
      (node (ref "R17") (pin "2") (pinfunction "2_2") (pintype "passive"))
    )
    (net (code "68") (name "Net-(LED3-C)") (class "Default")
      (node (ref "LED3") (pin "K") (pinfunction "C_K") (pintype "passive"))
      (node (ref "Q24") (pin "1") (pinfunction "ANODE_1") (pintype "passive"))
    )
    (net (code "69") (name "Net-(LED3-PadA)") (class "Default")
      (node (ref "LED3") (pin "A") (pinfunction "A_A") (pintype "passive"))
      (node (ref "R20") (pin "2") (pinfunction "2_2") (pintype "passive"))
    )
    (net (code "70") (name "Net-(LED4-C)") (class "Default")
      (node (ref "LED4") (pin "K") (pinfunction "C_K") (pintype "passive"))
      (node (ref "Q25") (pin "1") (pinfunction "ANODE_1") (pintype "passive"))
    )
    (net (code "71") (name "Net-(LED4-PadA)") (class "Default")
      (node (ref "LED4") (pin "A") (pinfunction "A_A") (pintype "passive"))
      (node (ref "R25") (pin "2") (pinfunction "2_2") (pintype "passive"))
    )
    (net (code "72") (name "Net-(LED6-C)") (class "Default")
      (node (ref "LED6") (pin "K") (pinfunction "C_K") (pintype "passive"))
      (node (ref "R3") (pin "2") (pinfunction "2_2") (pintype "passive"))
    )
    (net (code "73") (name "Net-(LED7-C)") (class "Default")
      (node (ref "LED7") (pin "K") (pinfunction "C_K") (pintype "passive"))
      (node (ref "R4") (pin "2") (pinfunction "2_2") (pintype "passive"))
    )
    (net (code "74") (name "Net-(LED8-C)") (class "Default")
      (node (ref "LED8") (pin "K") (pinfunction "C_K") (pintype "passive"))
      (node (ref "R7") (pin "2") (pinfunction "2_2") (pintype "passive"))
    )
    (net (code "75") (name "Net-(LED9-C)") (class "Default")
      (node (ref "LED9") (pin "K") (pinfunction "C_K") (pintype "passive"))
      (node (ref "R10") (pin "2") (pinfunction "2_2") (pintype "passive"))
    )
    (net (code "76") (name "Net-(Q13-G)") (class "Default")
      (node (ref "13V_ZENER") (pin "A") (pinfunction "A_A") (pintype "passive"))
      (node (ref "Q13") (pin "1") (pinfunction "G_1") (pintype "passive"))
      (node (ref "R5") (pin "2") (pinfunction "2_2") (pintype "passive"))
    )
    (net (code "77") (name "Net-(Q14-G)") (class "Default")
      (node (ref "13V_ZENER1") (pin "A") (pinfunction "A_A") (pintype "passive"))
      (node (ref "Q14") (pin "1") (pinfunction "G_1") (pintype "passive"))
      (node (ref "R6") (pin "2") (pinfunction "2_2") (pintype "passive"))
    )
    (net (code "78") (name "Net-(R12-Pad1)") (class "Default")
      (node (ref "R12") (pin "1") (pinfunction "1_1") (pintype "passive"))
      (node (ref "R13") (pin "2") (pinfunction "2_2") (pintype "passive"))
      (node (ref "R14") (pin "1") (pinfunction "1_1") (pintype "passive"))
    )
    (net (code "79") (name "Net-(R17-Pad1)") (class "Default")
      (node (ref "R17") (pin "1") (pinfunction "1_1") (pintype "passive"))
      (node (ref "R18") (pin "2") (pinfunction "2_2") (pintype "passive"))
      (node (ref "R19") (pin "1") (pinfunction "1_1") (pintype "passive"))
    )
    (net (code "80") (name "Net-(R20-Pad1)") (class "Default")
      (node (ref "R20") (pin "1") (pinfunction "1_1") (pintype "passive"))
      (node (ref "R21") (pin "2") (pinfunction "2_2") (pintype "passive"))
      (node (ref "R24") (pin "1") (pinfunction "1_1") (pintype "passive"))
    )
    (net (code "81") (name "Net-(R25-Pad1)") (class "Default")
      (node (ref "R25") (pin "1") (pinfunction "1_1") (pintype "passive"))
      (node (ref "R26") (pin "2") (pinfunction "2_2") (pintype "passive"))
      (node (ref "R27") (pin "1") (pinfunction "1_1") (pintype "passive"))
    )
    (net (code "82") (name "unconnected-(STM_BLUEPILL-3.3V1-PadP$20)") (class "Default")
      (node (ref "STM_BLUEPILL") (pin "P$20") (pinfunction "3.3V1_P$20") (pintype "bidirectional"))
    )
    (net (code "83") (name "unconnected-(STM_BLUEPILL-GND2-PadP$19)") (class "Default")
      (node (ref "STM_BLUEPILL") (pin "P$19") (pinfunction "GND2_P$19") (pintype "bidirectional"))
    )
    (net (code "84") (name "unconnected-(STM_BLUEPILL-PC13-PadP$39)") (class "Default")
      (node (ref "STM_BLUEPILL") (pin "P$39") (pinfunction "PC13_P$39") (pintype "bidirectional"))
    )
    (net (code "85") (name "unconnected-(STM_BLUEPILL-PC14-PadP$38)") (class "Default")
      (node (ref "STM_BLUEPILL") (pin "P$38") (pinfunction "PC14_P$38") (pintype "bidirectional"))
    )
    (net (code "86") (name "unconnected-(STM_BLUEPILL-PC15-PadP$37)") (class "Default")
      (node (ref "STM_BLUEPILL") (pin "P$37") (pinfunction "PC15_P$37") (pintype "bidirectional"))
    )
    (net (code "87") (name "unconnected-(STM_BLUEPILL-VBAT-PadP$40)") (class "Default")
      (node (ref "STM_BLUEPILL") (pin "P$40") (pinfunction "VBAT_P$40") (pintype "bidirectional"))
    )
    (net (code "88") (name "unconnected-(U$2-PadNC)") (class "Default")
      (node (ref "U$2") (pin "NC") (pinfunction "NC_NC") (pintype "passive"))
    )
    (net (code "89") (name "unconnected-(U$23-Pad7)") (class "Default")
      (node (ref "U$23") (pin "7") (pinfunction "7_7") (pintype "passive"))
    )
    (net (code "90") (name "unconnected-(U$23-Pad8)") (class "Default")
      (node (ref "U$23") (pin "8") (pinfunction "8_8") (pintype "passive"))
    )
    (net (code "91") (name "unconnected-(U$27-Pad2)") (class "Default")
      (node (ref "U$27") (pin "2") (pinfunction "2_2") (pintype "bidirectional"))
    )
    (net (code "92") (name "unconnected-(U$28-Pad2)") (class "Default")
      (node (ref "U$28") (pin "2") (pinfunction "2_2") (pintype "bidirectional"))
    )
  )
)
